# Black_OC_jr7.net
KiCad netlist of a schematic drawn in EAGLE
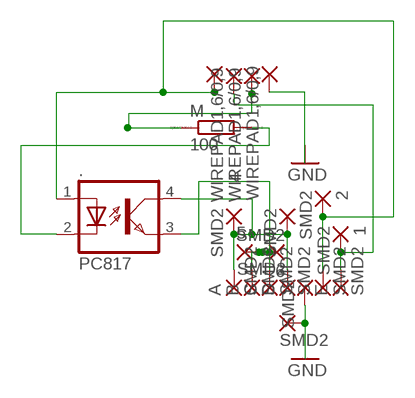
[diagram p0: schematic, sheet 1]

(export (version "E")
  (design (tool "Eeschema 10.0.6"))
  (components
    (comp (ref "+")
      (value "SMD2")
      (footprint "eagle-import:SMD1,27-2,54")
      (libsource (lib "eagle-import") (part "SMD2"))
    )
    (comp (ref "-")
      (value "SMD2")
      (footprint "eagle-import:SMD1,27-2,54")
      (libsource (lib "eagle-import") (part "SMD2"))
    )
    (comp (ref "--")
      (value "1,6/0,9")
      (footprint "eagle-import:1,6_0,9")
      (libsource (lib "eagle-import") (part "1,6/0,9"))
    )
    (comp (ref "---")
      (value "WIREPAD1,6/0,9")
      (footprint "eagle-import:1,6_0,9")
      (libsource (lib "eagle-import") (part "WIREPAD1,6/0,9"))
    )
    (comp (ref "----")
      (value "WIREPAD1,6/0,9")
      (footprint "eagle-import:1,6_0,9")
      (libsource (lib "eagle-import") (part "WIREPAD1,6/0,9"))
    )
    (comp (ref "-----")
      (value "WIREPAD1,6/0,9")
      (footprint "eagle-import:1,6_0,9")
      (libsource (lib "eagle-import") (part "WIREPAD1,6/0,9"))
    )
    (comp (ref ".")
      (value "PC817")
      (footprint "eagle-import:DIL04")
      (fields (field (name "MPN") "PC817X4J000F"))
      (libsource (lib "eagle-import") (part "PC817"))
    )
    (comp (ref "...")
      (value "SMD2")
      (footprint "eagle-import:SMD1,27-2,54")
      (libsource (lib "eagle-import") (part "SMD2"))
    )
    (comp (ref "1")
      (value "SMD2")
      (footprint "eagle-import:SMD1,27-2,54")
      (libsource (lib "eagle-import") (part "SMD2"))
    )
    (comp (ref "2")
      (value "SMD2")
      (footprint "eagle-import:SMD1,27-2,54")
      (libsource (lib "eagle-import") (part "SMD2"))
    )
    (comp (ref "4")
      (value "SMD2")
      (footprint "eagle-import:SMD1,27-2,54")
      (libsource (lib "eagle-import") (part "SMD2"))
    )
    (comp (ref "5")
      (value "SMD2")
      (footprint "eagle-import:SMD1,27-2,54")
      (libsource (lib "eagle-import") (part "SMD2"))
    )
    (comp (ref "6")
      (value "SMD2")
      (footprint "eagle-import:SMD1,27-2,54")
      (libsource (lib "eagle-import") (part "SMD2"))
    )
    (comp (ref "A")
      (value "SMD2")
      (footprint "eagle-import:SMD1,27-2,54")
      (libsource (lib "eagle-import") (part "SMD2"))
    )
    (comp (ref "B")
      (value "SMD2")
      (footprint "eagle-import:SMD1,27-2,54")
      (libsource (lib "eagle-import") (part "SMD2"))
    )
    (comp (ref "C")
      (value "SMD2")
      (footprint "eagle-import:SMD1,27-2,54")
      (libsource (lib "eagle-import") (part "SMD2"))
    )
    (comp (ref "D")
      (value "SMD2")
      (footprint "eagle-import:SMD1,27-2,54")
      (libsource (lib "eagle-import") (part "SMD2"))
    )
    (comp (ref "E")
      (value "SMD2")
      (footprint "eagle-import:SMD1,27-2,54")
      (libsource (lib "eagle-import") (part "SMD2"))
    )
    (comp (ref "M")
      (value "100")
      (footprint "eagle-import:0204_7")
      (libsource (lib "eagle-import") (part "R0204/7"))
    )
    (comp (ref "PAD7")
      (value "SMD2")
      (footprint "eagle-import:SMD1,27-2,54")
      (libsource (lib "eagle-import") (part "SMD2"))
    )
  )
  (nets
    (net (code "1") (name "GND") (class "Default")
      (node (ref "-") (pin "1") (pinfunction "P_1") (pintype "passive"))
      (node (ref "-----") (pin "1") (pinfunction "P_1") (pintype "passive"))
      (node (ref "PAD7") (pin "1") (pinfunction "P_1") (pintype "passive"))
    )
    (net (code "2") (name "Net-(+-P)") (class "Default")
      (node (ref "+") (pin "1") (pinfunction "P_1") (pintype "passive"))
      (node (ref "--") (pin "1") (pinfunction "P_1") (pintype "passive"))
      (node (ref ".") (pin "1") (pinfunction "A_1") (pintype "passive"))
      (node (ref "2") (pin "1") (pinfunction "P_1") (pintype "passive"))
    )
    (net (code "3") (name "Net-(-----P)") (class "Default")
      (node (ref "----") (pin "1") (pinfunction "P_1") (pintype "passive"))
      (node (ref "M") (pin "1") (pinfunction "1_1") (pintype "passive"))
    )
    (net (code "4") (name "Net-(----P)") (class "Default")
      (node (ref "---") (pin "1") (pinfunction "P_1") (pintype "passive"))
      (node (ref "1") (pin "1") (pinfunction "P_1") (pintype "passive"))
      (node (ref "E") (pin "1") (pinfunction "P_1") (pintype "passive"))
    )
    (net (code "5") (name "Net-(.-C)") (class "Default")
      (node (ref ".") (pin "2") (pinfunction "C_2") (pintype "passive"))
      (node (ref "M") (pin "2") (pinfunction "2_2") (pintype "passive"))
    )
    (net (code "6") (name "Net-(.-COL)") (class "Default")
      (node (ref ".") (pin "4") (pinfunction "COL_4") (pintype "passive"))
      (node (ref "...") (pin "1") (pinfunction "P_1") (pintype "passive"))
      (node (ref "4") (pin "1") (pinfunction "P_1") (pintype "passive"))
      (node (ref "A") (pin "1") (pinfunction "P_1") (pintype "passive"))
      (node (ref "D") (pin "1") (pinfunction "P_1") (pintype "passive"))
    )
    (net (code "7") (name "Net-(.-EMIT)") (class "Default")
      (node (ref ".") (pin "3") (pinfunction "EMIT_3") (pintype "passive"))
      (node (ref "5") (pin "1") (pinfunction "P_1") (pintype "passive"))
      (node (ref "6") (pin "1") (pinfunction "P_1") (pintype "passive"))
      (node (ref "B") (pin "1") (pinfunction "P_1") (pintype "passive"))
      (node (ref "C") (pin "1") (pinfunction "P_1") (pintype "passive"))
    )
  )
)
